# nled-dis-oled-v1a.net
KiCad netlist of a schematic drawn in EAGLE
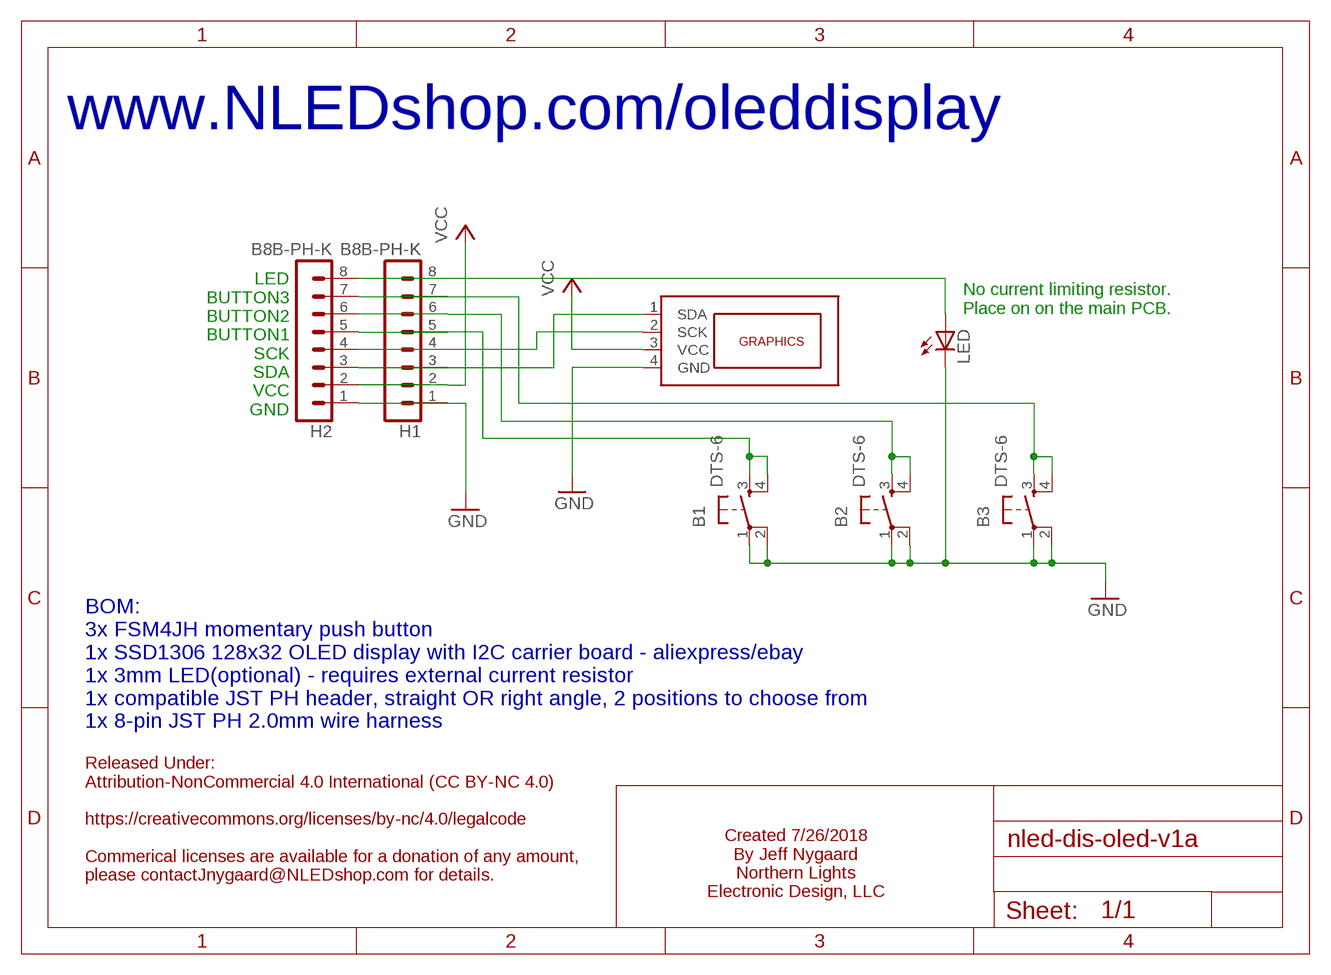
[diagram p0: schematic, sheet 1]

(export (version "E")
  (design (tool "Eeschema 10.0.6"))
  (components
    (comp (ref "B1")
      (value "DTS-6")
      (footprint "eagle-import:DTS-6")
      (libsource (lib "eagle-import") (part "DTS-6"))
    )
    (comp (ref "B2")
      (value "DTS-6")
      (footprint "eagle-import:DTS-6")
      (libsource (lib "eagle-import") (part "DTS-6"))
    )
    (comp (ref "B3")
      (value "DTS-6")
      (footprint "eagle-import:DTS-6")
      (libsource (lib "eagle-import") (part "DTS-6"))
    )
    (comp (ref "H1")
      (value "B8B-PH-K")
      (footprint "eagle-import:B8B-PH-K")
      (libsource (lib "eagle-import") (part "B8B-PH-K"))
    )
    (comp (ref "H2")
      (value "B8B-PH-K")
      (footprint "eagle-import:B8B-PH-K")
      (libsource (lib "eagle-import") (part "B8B-PH-K"))
    )
    (comp (ref "LED")
      (value "LED3MM")
      (footprint "eagle-import:LED3MM")
      (libsource (lib "eagle-import") (part "LED3MM"))
    )
    (comp (ref "OLED")
      (value "OLED-128X32")
      (footprint "eagle-import:OLED-128X32")
      (libsource (lib "eagle-import") (part "OLED-128X32"))
    )
  )
  (nets
    (net (code "1") (name "GND") (class "Default")
      (node (ref "B1") (pin "1") (pinfunction "1_1") (pintype "passive"))
      (node (ref "B1") (pin "2") (pinfunction "2_2") (pintype "passive"))
      (node (ref "B2") (pin "1") (pinfunction "1_1") (pintype "passive"))
      (node (ref "B2") (pin "2") (pinfunction "2_2") (pintype "passive"))
      (node (ref "B3") (pin "1") (pinfunction "1_1") (pintype "passive"))
      (node (ref "B3") (pin "2") (pinfunction "2_2") (pintype "passive"))
      (node (ref "H1") (pin "1") (pinfunction "1_1") (pintype "passive"))
      (node (ref "H2") (pin "1") (pinfunction "1_1") (pintype "passive"))
      (node (ref "LED") (pin "K") (pinfunction "C_K") (pintype "passive"))
      (node (ref "OLED") (pin "4") (pinfunction "GND_4") (pintype "bidirectional"))
    )
    (net (code "2") (name "Net-(B1-Pad3)") (class "Default")
      (node (ref "B1") (pin "3") (pinfunction "3_3") (pintype "passive"))
      (node (ref "B1") (pin "4") (pinfunction "4_4") (pintype "passive"))
      (node (ref "H1") (pin "5") (pinfunction "5_5") (pintype "passive"))
      (node (ref "H2") (pin "5") (pinfunction "5_5") (pintype "passive"))
    )
    (net (code "3") (name "Net-(B2-Pad3)") (class "Default")
      (node (ref "B2") (pin "3") (pinfunction "3_3") (pintype "passive"))
      (node (ref "B2") (pin "4") (pinfunction "4_4") (pintype "passive"))
      (node (ref "H1") (pin "6") (pinfunction "6_6") (pintype "passive"))
      (node (ref "H2") (pin "6") (pinfunction "6_6") (pintype "passive"))
    )
    (net (code "4") (name "Net-(B3-Pad3)") (class "Default")
      (node (ref "B3") (pin "3") (pinfunction "3_3") (pintype "passive"))
      (node (ref "B3") (pin "4") (pinfunction "4_4") (pintype "passive"))
      (node (ref "H1") (pin "7") (pinfunction "7_7") (pintype "passive"))
      (node (ref "H2") (pin "7") (pinfunction "7_7") (pintype "passive"))
    )
    (net (code "5") (name "Net-(H1-Pad8)") (class "Default")
      (node (ref "H1") (pin "8") (pinfunction "8_8") (pintype "passive"))
      (node (ref "H2") (pin "8") (pinfunction "8_8") (pintype "passive"))
      (node (ref "LED") (pin "A") (pinfunction "A_A") (pintype "passive"))
    )
    (net (code "6") (name "Net-(OLED-SCK)") (class "Default")
      (node (ref "H1") (pin "4") (pinfunction "4_4") (pintype "passive"))
      (node (ref "H2") (pin "4") (pinfunction "4_4") (pintype "passive"))
      (node (ref "OLED") (pin "2") (pinfunction "SCK_2") (pintype "bidirectional"))
    )
    (net (code "7") (name "Net-(OLED-SDA)") (class "Default")
      (node (ref "H1") (pin "3") (pinfunction "3_3") (pintype "passive"))
      (node (ref "H2") (pin "3") (pinfunction "3_3") (pintype "passive"))
      (node (ref "OLED") (pin "1") (pinfunction "SDA_1") (pintype "bidirectional"))
    )
    (net (code "8") (name "VCC") (class "Default")
      (node (ref "H1") (pin "2") (pinfunction "2_2") (pintype "passive"))
      (node (ref "H2") (pin "2") (pinfunction "2_2") (pintype "passive"))
      (node (ref "OLED") (pin "3") (pinfunction "VCC_3") (pintype "bidirectional"))
    )
  )
)
